# SwitchUniControl.net
KiCad netlist of a schematic drawn in Altium Designer
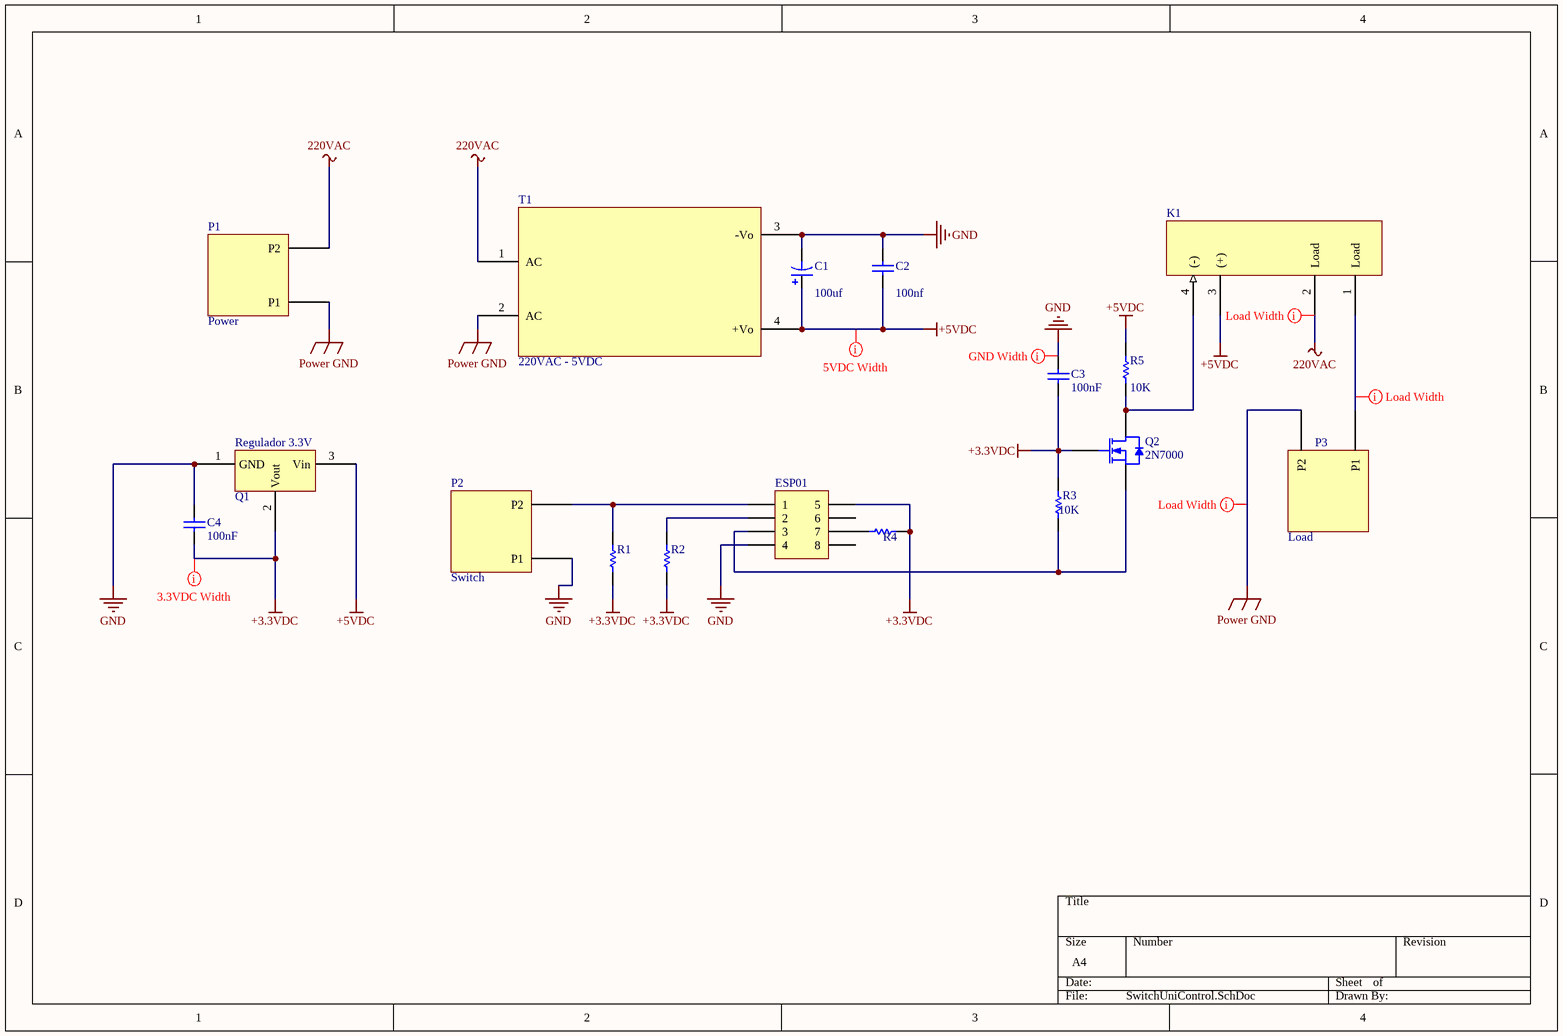
[diagram p0: SwitchUniControl.SchDoc]

(export (version "E")
  (design (tool "Eeschema 10.0.6"))
  (components
    (comp (ref "C1")
      (value "100uf")
      (footprint "RAD-0.1")
      (description "Polarized Capacitor (Radial)")
      (fields (field (name "Comment") "Cap Pol1") (field (name "PUBLISHER") "Altium Limited"))
      (libsource (lib "Miscellaneous Devices") (part "Cap Pol1"))
    )
    (comp (ref "C2")
      (value "100nf")
      (footprint "RAD-0.1")
      (description "Capacitor")
      (fields (field (name "Comment") "Cap") (field (name "PUBLISHER") "Altium Limited"))
      (libsource (lib "Miscellaneous Devices") (part "Cap"))
    )
    (comp (ref "C3")
      (value "100nF")
      (footprint "RAD-0.1")
      (description "Capacitor")
      (fields (field (name "Comment") "Cap") (field (name "PUBLISHER") "Altium Limited"))
      (libsource (lib "Miscellaneous Devices") (part "Cap"))
    )
    (comp (ref "C4")
      (value "100nF")
      (footprint "RAD-0.1")
      (description "Capacitor")
      (fields (field (name "Comment") "Cap") (field (name "PUBLISHER") "Altium Limited"))
      (libsource (lib "Miscellaneous Devices") (part "Cap"))
    )
    (comp (ref "ESP01")
      (value "Header 4X2A")
      (footprint "HDR2X4_CEN")
      (description "Header, 4-Pin, Dual row")
      (fields (field (name "PUBLISHER") "Altium Limited"))
      (libsource (lib "Miscellaneous Connectors") (part "Header 4X2A"))
    )
    (comp (ref "K1")
      (value "G3MB-202P DC5")
      (footprint "G3MB-202P DC5")
      (description "RELAY MINI SSR 240VAC@2A ZERO")
      (fields (field (name "MFR") "Omron"))
      (libsource (lib "G3MB-202P") (part "G3MB-202P DC5"))
    )
    (comp (ref "P1")
      (value "Power")
      (footprint "ScrewTerminal-X2")
      (libsource (lib "") (part "ScrewTerminal_1"))
    )
    (comp (ref "P2")
      (value "Switch")
      (footprint "ScrewTerminal-X2")
      (libsource (lib "") (part "ScrewTerminal_1"))
    )
    (comp (ref "P3")
      (value "Load")
      (footprint "ScrewTerminal-X2")
      (libsource (lib "ScrewTerminal_2X") (part "ScrewTerminal"))
    )
    (comp (ref "Q1")
      (value "Regulador 3.3V")
      (footprint "TO220")
      (libsource (lib "AMS1117") (part "AMS1117"))
    )
    (comp (ref "Q2")
      (value "2N7000")
      (footprint "SOT54")
      (description "N-channel Enhancement Mode Field-effect Transistor")
      (fields (field (name "PUBLISHER") "Altium Limited"))
      (libsource (lib "Philips Discrete MOSFET - Low Power") (part "2N7000"))
    )
    (comp (ref "R1")
      (value "Res1")
      (footprint "AXIAL-0.3")
      (description "Resistor")
      (fields (field (name "PUBLISHER") "Altium Limited"))
      (libsource (lib "Miscellaneous Devices") (part "Res1"))
    )
    (comp (ref "R2")
      (value "Res1")
      (footprint "AXIAL-0.3")
      (description "Resistor")
      (fields (field (name "PUBLISHER") "Altium Limited"))
      (libsource (lib "Miscellaneous Devices") (part "Res1"))
    )
    (comp (ref "R3")
      (value "10K")
      (footprint "AXIAL-0.3")
      (description "Resistor")
      (fields (field (name "Comment") "Res1") (field (name "PUBLISHER") "Altium Limited"))
      (libsource (lib "Miscellaneous Devices") (part "Res1"))
    )
    (comp (ref "R4")
      (value "Res1")
      (footprint "AXIAL-0.3")
      (description "Resistor")
      (fields (field (name "PUBLISHER") "Altium Limited"))
      (libsource (lib "Miscellaneous Devices") (part "Res1"))
    )
    (comp (ref "R5")
      (value "10K")
      (footprint "AXIAL-0.3")
      (description "Resistor")
      (fields (field (name "Comment") "Res1") (field (name "PUBLISHER") "Altium Limited"))
      (libsource (lib "Miscellaneous Devices") (part "Res1"))
    )
    (comp (ref "T1")
      (value "220VAC - 5VDC")
      (footprint "HLK-PM")
      (description "HLK-PM*")
      (fields (field (name "MFR") "HLK-PM01"))
      (libsource (lib "HLK-PM") (part "HLK-PM"))
    )
  )
  (nets
    (net (code "1") (name "+3.3VDC") (class "Default")
      (node (ref "C3") (pin "2") (pinfunction "2_2") (pintype "passive"))
      (node (ref "C4") (pin "2") (pinfunction "2_2") (pintype "passive"))
      (node (ref "ESP01") (pin "5") (pinfunction "5_5") (pintype "passive"))
      (node (ref "Q1") (pin "2") (pinfunction "Vout_2") (pintype "passive"))
      (node (ref "Q2") (pin "2") (pinfunction "G_2") (pintype "passive"))
      (node (ref "R1") (pin "1") (pinfunction "1_1") (pintype "passive"))
      (node (ref "R2") (pin "1") (pinfunction "1_1") (pintype "passive"))
      (node (ref "R3") (pin "2") (pinfunction "2_2") (pintype "passive"))
      (node (ref "R4") (pin "2") (pinfunction "2_2") (pintype "passive"))
    )
    (net (code "2") (name "+5VDC") (class "Default")
      (node (ref "C1") (pin "1") (pinfunction "1_1") (pintype "passive"))
      (node (ref "C2") (pin "1") (pinfunction "1_1") (pintype "passive"))
      (node (ref "K1") (pin "3") (pinfunction "(+)_3") (pintype "power_in"))
      (node (ref "Q1") (pin "3") (pinfunction "Vin_3") (pintype "passive"))
      (node (ref "R5") (pin "2") (pinfunction "2_2") (pintype "passive"))
      (node (ref "T1") (pin "4") (pinfunction "+Vo_4") (pintype "passive"))
    )
    (net (code "3") (name "220VAC") (class "Default")
      (node (ref "K1") (pin "2") (pinfunction "Load_2") (pintype "passive"))
      (node (ref "P1") (pin "2") (pinfunction "P2_2") (pintype "passive"))
      (node (ref "T1") (pin "1") (pinfunction "AC_1") (pintype "power_in"))
    )
    (net (code "4") (name "GND") (class "Default")
      (node (ref "C1") (pin "2") (pinfunction "2_2") (pintype "passive"))
      (node (ref "C2") (pin "2") (pinfunction "2_2") (pintype "passive"))
      (node (ref "C3") (pin "1") (pinfunction "1_1") (pintype "passive"))
      (node (ref "C4") (pin "1") (pinfunction "1_1") (pintype "passive"))
      (node (ref "ESP01") (pin "4") (pinfunction "4_4") (pintype "passive"))
      (node (ref "P2") (pin "1") (pinfunction "P1_1") (pintype "passive"))
      (node (ref "Q1") (pin "1") (pinfunction "GND_1") (pintype "passive"))
      (node (ref "T1") (pin "3") (pinfunction "-Vo_3") (pintype "passive"))
    )
    (net (code "5") (name "Net-(ESP01-Pad2)") (class "Default")
      (node (ref "ESP01") (pin "2") (pinfunction "2_2") (pintype "passive"))
      (node (ref "R2") (pin "2") (pinfunction "2_2") (pintype "passive"))
    )
    (net (code "6") (name "Net-(ESP01-Pad7)") (class "Default")
      (node (ref "ESP01") (pin "7") (pinfunction "7_7") (pintype "passive"))
      (node (ref "R4") (pin "1") (pinfunction "1_1") (pintype "passive"))
    )
    (net (code "7") (name "Net-(K1-(-))") (class "Default")
      (node (ref "K1") (pin "4") (pinfunction "(-)_4") (pintype "input"))
      (node (ref "Q2") (pin "1") (pinfunction "D_1") (pintype "passive"))
      (node (ref "R5") (pin "1") (pinfunction "1_1") (pintype "passive"))
    )
    (net (code "8") (name "Net-(P2-P2)") (class "Default")
      (node (ref "ESP01") (pin "1") (pinfunction "1_1") (pintype "passive"))
      (node (ref "P2") (pin "2") (pinfunction "P2_2") (pintype "passive"))
      (node (ref "R1") (pin "2") (pinfunction "2_2") (pintype "passive"))
    )
    (net (code "9") (name "Net-(P3-P1)") (class "Default")
      (node (ref "K1") (pin "1") (pinfunction "Load_1") (pintype "passive"))
      (node (ref "P3") (pin "1") (pinfunction "P1_1") (pintype "passive"))
    )
    (net (code "10") (name "Net-(Q2-S)") (class "Default")
      (node (ref "ESP01") (pin "3") (pinfunction "3_3") (pintype "passive"))
      (node (ref "Q2") (pin "3") (pinfunction "S_3") (pintype "passive"))
      (node (ref "R3") (pin "1") (pinfunction "1_1") (pintype "passive"))
    )
    (net (code "11") (name "Power GND") (class "Default")
      (node (ref "P1") (pin "1") (pinfunction "P1_1") (pintype "passive"))
      (node (ref "P3") (pin "2") (pinfunction "P2_2") (pintype "passive"))
      (node (ref "T1") (pin "2") (pinfunction "AC_2") (pintype "power_in"))
    )
    (net (code "12") (name "unconnected-(ESP01-Pad6)") (class "Default")
      (node (ref "ESP01") (pin "6") (pinfunction "6_6") (pintype "passive"))
    )
    (net (code "13") (name "unconnected-(ESP01-Pad8)") (class "Default")
      (node (ref "ESP01") (pin "8") (pinfunction "8_8") (pintype "passive"))
    )
  )
)
